# SparkFun_Qwiic_FS3000.net
KiCad netlist of a schematic drawn in EAGLE
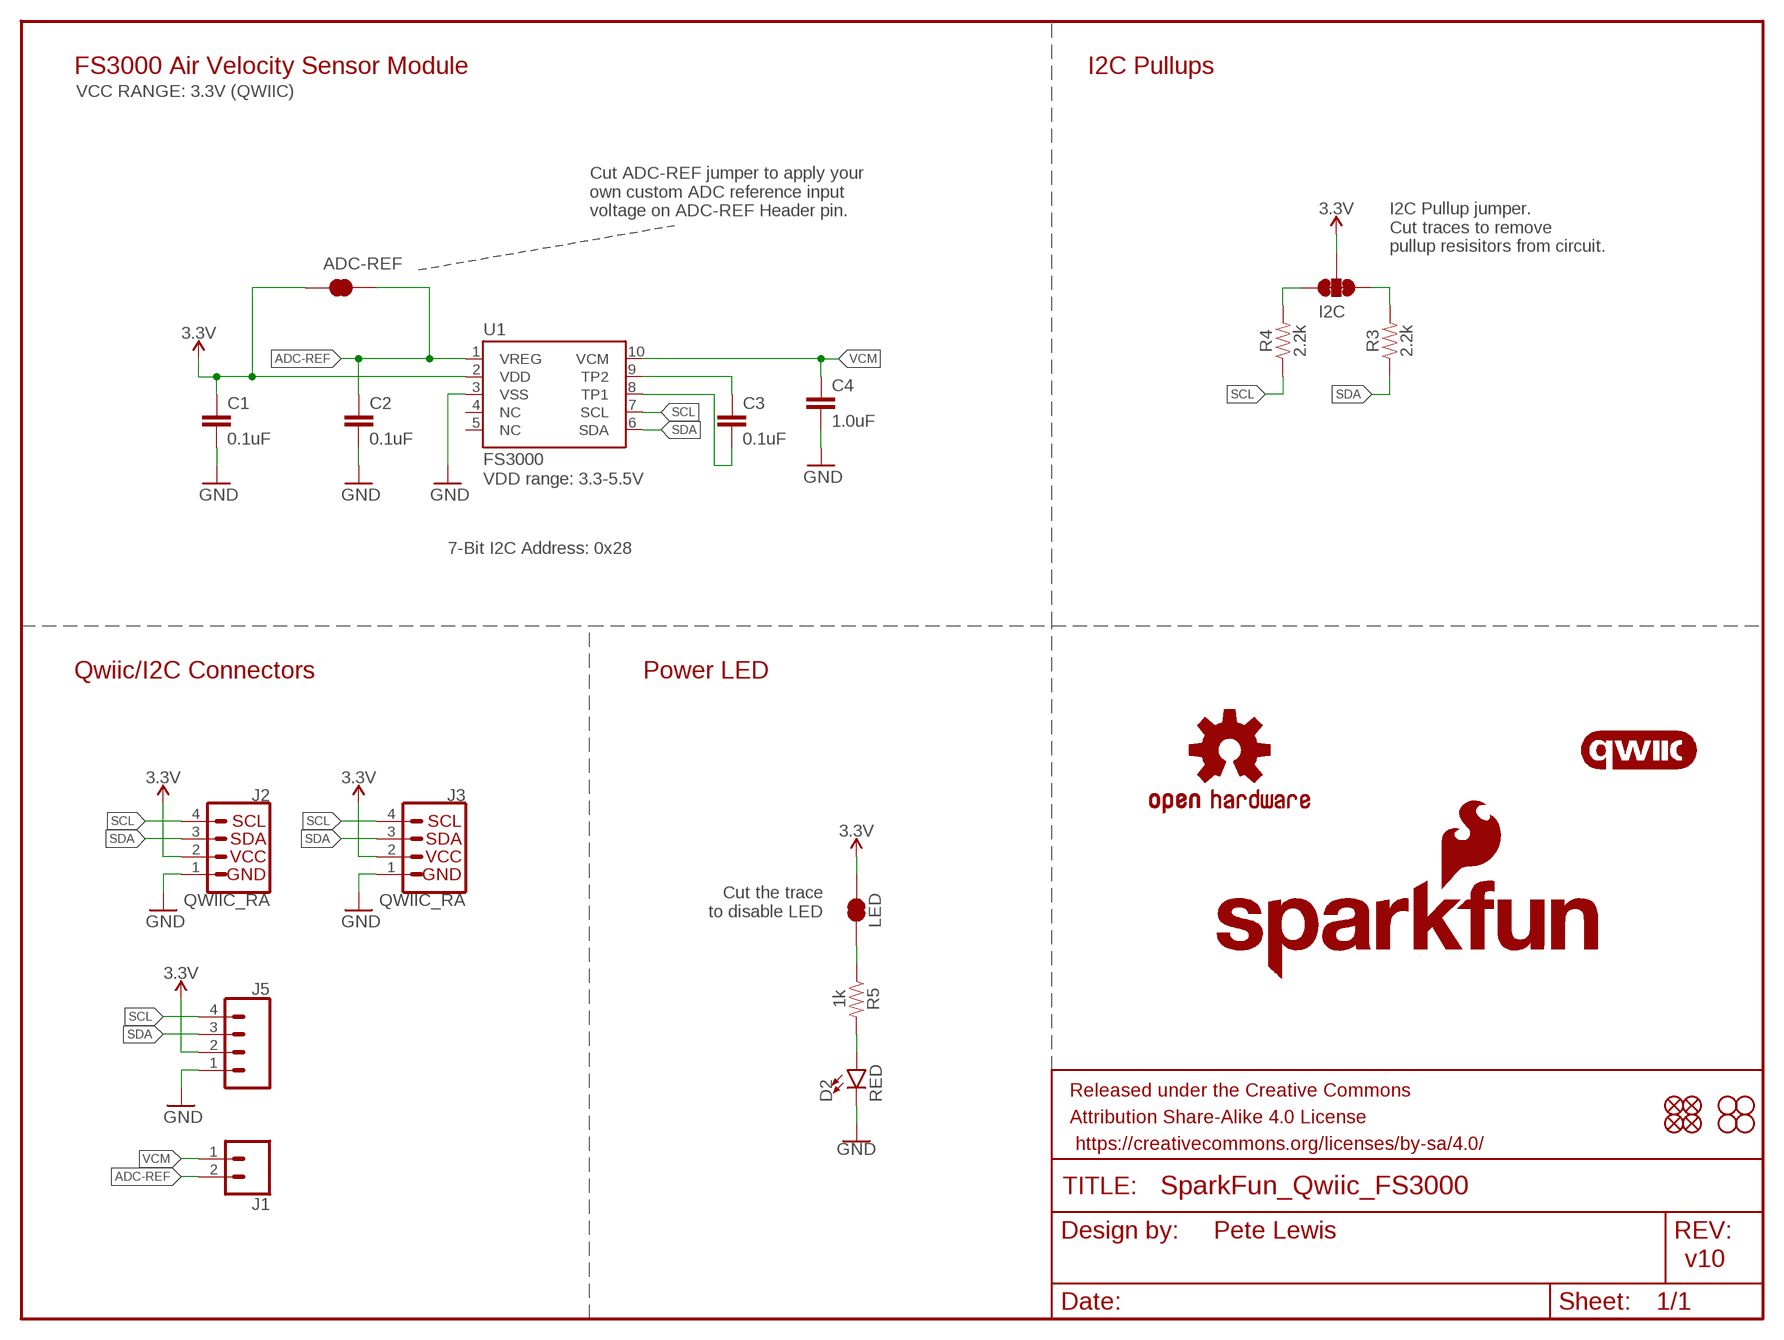
[diagram p0: schematic, sheet 1]

(export (version "E")
  (design (tool "Eeschema 10.0.6"))
  (components
    (comp (ref "ADC-REF")
      (value "JUMPER-SMT_2_NC_TRACE_SILK")
      (footprint "eagle-import:SMT-JUMPER_2_NC_TRACE_SILK")
      (libsource (lib "eagle-import") (part "JUMPER-SMT_2_NC_TRACE_SILK"))
    )
    (comp (ref "C1")
      (value "0.1uF")
      (footprint "eagle-import:0402-TIGHT")
      (libsource (lib "eagle-import") (part "0.1UF-0402T-16V-10%"))
    )
    (comp (ref "C2")
      (value "0.1uF")
      (footprint "eagle-import:0402-TIGHT")
      (libsource (lib "eagle-import") (part "0.1UF-0402T-16V-10%"))
    )
    (comp (ref "C3")
      (value "0.1uF")
      (footprint "eagle-import:0402-TIGHT")
      (libsource (lib "eagle-import") (part "0.1UF-0402T-16V-10%"))
    )
    (comp (ref "C4")
      (value "1.0uF")
      (footprint "eagle-import:0402-TIGHT")
      (libsource (lib "eagle-import") (part "1.0UF-0402T-16V-10%"))
    )
    (comp (ref "D2")
      (value "RED")
      (footprint "eagle-import:LED-0603")
      (libsource (lib "eagle-import") (part "LED-RED0603"))
    )
    (comp (ref "FRAME1")
      (value "FRAME-LETTER")
      (footprint "eagle-import:CREATIVE_COMMONS")
      (libsource (lib "eagle-import") (part "FRAME-LETTER"))
    )
    (comp (ref "I2C")
      (value "JUMPER-SMT_3_2-NC_TRACE_SILK")
      (footprint "eagle-import:SMT-JUMPER_3_2-NC_TRACE_SILK")
      (libsource (lib "eagle-import") (part "JUMPER-SMT_3_2-NC_TRACE_SILK"))
    )
    (comp (ref "J1")
      (value "CONN_021X02_NO_SILK")
      (footprint "eagle-import:1X02_NO_SILK")
      (libsource (lib "eagle-import") (part "CONN_021X02_NO_SILK"))
    )
    (comp (ref "J2")
      (value "QWIIC_RA")
      (footprint "eagle-import:JST04_1MM_RA")
      (libsource (lib "eagle-import") (part "QWIIC_CONNECTORJS-1MM"))
    )
    (comp (ref "J3")
      (value "QWIIC_RA")
      (footprint "eagle-import:JST04_1MM_RA")
      (libsource (lib "eagle-import") (part "QWIIC_CONNECTORJS-1MM"))
    )
    (comp (ref "J5")
      (value "CONN_041X04_NO_SILK")
      (footprint "eagle-import:1X04_NO_SILK")
      (libsource (lib "eagle-import") (part "CONN_041X04_NO_SILK"))
    )
    (comp (ref "JP1")
      (value "LED")
      (footprint "eagle-import:SMT-JUMPER_2_NC_TRACE_SILK")
      (libsource (lib "eagle-import") (part "JUMPER-SMT_2_NC_TRACE_SILK"))
    )
    (comp (ref "JP2")
      (value "FIDUCIALUFIDUCIAL")
      (footprint "eagle-import:FIDUCIAL-MICRO")
      (libsource (lib "eagle-import") (part "FIDUCIALUFIDUCIAL"))
    )
    (comp (ref "JP3")
      (value "STAND-OFF")
      (footprint "eagle-import:STAND-OFF")
      (libsource (lib "eagle-import") (part "STAND-OFF"))
    )
    (comp (ref "JP4")
      (value "STAND-OFF")
      (footprint "eagle-import:STAND-OFF")
      (libsource (lib "eagle-import") (part "STAND-OFF"))
    )
    (comp (ref "JP5")
      (value "FIDUCIALUFIDUCIAL")
      (footprint "eagle-import:FIDUCIAL-MICRO")
      (libsource (lib "eagle-import") (part "FIDUCIALUFIDUCIAL"))
    )
    (comp (ref "JP6")
      (value "FIDUCIALUFIDUCIAL")
      (footprint "eagle-import:FIDUCIAL-MICRO")
      (libsource (lib "eagle-import") (part "FIDUCIALUFIDUCIAL"))
    )
    (comp (ref "JP7")
      (value "STAND-OFF")
      (footprint "eagle-import:STAND-OFF")
      (libsource (lib "eagle-import") (part "STAND-OFF"))
    )
    (comp (ref "JP8")
      (value "STAND-OFF")
      (footprint "eagle-import:STAND-OFF")
      (libsource (lib "eagle-import") (part "STAND-OFF"))
    )
    (comp (ref "JP11")
      (value "FIDUCIALUFIDUCIAL")
      (footprint "eagle-import:FIDUCIAL-MICRO")
      (libsource (lib "eagle-import") (part "FIDUCIALUFIDUCIAL"))
    )
    (comp (ref "LOGO1")
      (value "OSHW-LOGOMINI")
      (footprint "eagle-import:OSHW-LOGO-MINI")
      (libsource (lib "eagle-import") (part "OSHW-LOGOMINI"))
    )
    (comp (ref "LOGO3")
      (value "SFE_LOGO_NAME_FLAME.1_INCH")
      (footprint "eagle-import:SFE_LOGO_NAME_FLAME_.1")
      (libsource (lib "eagle-import") (part "SFE_LOGO_NAME_FLAME.1_INCH"))
    )
    (comp (ref "LOGO4")
      (value "QWIIC_LOGO_5MM")
      (footprint "eagle-import:QWIIC_5MM")
      (libsource (lib "eagle-import") (part "QWIIC_LOGO_5MM"))
    )
    (comp (ref "LOGO5")
      (value "SFE_LOGO_NAME_FLAME.1_INCH")
      (footprint "eagle-import:SFE_LOGO_NAME_FLAME_.1")
      (libsource (lib "eagle-import") (part "SFE_LOGO_NAME_FLAME.1_INCH"))
    )
    (comp (ref "R3")
      (value "2.2k")
      (footprint "eagle-import:0402-TIGHT")
      (libsource (lib "eagle-import") (part "2.2KOHM-0402T-1/16W-1%"))
    )
    (comp (ref "R4")
      (value "2.2k")
      (footprint "eagle-import:0402-TIGHT")
      (libsource (lib "eagle-import") (part "2.2KOHM-0402T-1/16W-1%"))
    )
    (comp (ref "R5")
      (value "1k")
      (footprint "eagle-import:0402-TIGHT")
      (libsource (lib "eagle-import") (part "1KOHM-0402T-1/16W-1%"))
    )
    (comp (ref "U1")
      (value "FS3000")
      (footprint "eagle-import:FS3000")
      (libsource (lib "eagle-import") (part "FS3000"))
    )
  )
  (nets
    (net (code "1") (name "3.3V") (class "Default")
      (node (ref "ADC-REF") (pin "1") (pinfunction "1_1") (pintype "passive"))
      (node (ref "C1") (pin "1") (pinfunction "1_1") (pintype "passive"))
      (node (ref "I2C") (pin "2") (pinfunction "2_2") (pintype "passive"))
      (node (ref "J2") (pin "2") (pinfunction "2_2") (pintype "power_in"))
      (node (ref "J3") (pin "2") (pinfunction "2_2") (pintype "power_in"))
      (node (ref "J5") (pin "2") (pinfunction "2_2") (pintype "passive"))
      (node (ref "JP1") (pin "2") (pinfunction "2_2") (pintype "passive"))
      (node (ref "U1") (pin "2") (pinfunction "VDD_2") (pintype "bidirectional"))
    )
    (net (code "2") (name "ADC-REF") (class "Default")
      (node (ref "ADC-REF") (pin "2") (pinfunction "2_2") (pintype "passive"))
      (node (ref "C2") (pin "1") (pinfunction "1_1") (pintype "passive"))
      (node (ref "J1") (pin "2") (pinfunction "2_2") (pintype "passive"))
      (node (ref "U1") (pin "1") (pinfunction "VREG_1") (pintype "bidirectional"))
    )
    (net (code "3") (name "GND") (class "Default")
      (node (ref "C1") (pin "2") (pinfunction "2_2") (pintype "passive"))
      (node (ref "C2") (pin "2") (pinfunction "2_2") (pintype "passive"))
      (node (ref "C4") (pin "2") (pinfunction "2_2") (pintype "passive"))
      (node (ref "D2") (pin "C") (pinfunction "C_C") (pintype "passive"))
      (node (ref "J2") (pin "1") (pinfunction "1_1") (pintype "power_in"))
      (node (ref "J3") (pin "1") (pinfunction "1_1") (pintype "power_in"))
      (node (ref "J5") (pin "1") (pinfunction "1_1") (pintype "passive"))
      (node (ref "U1") (pin "3") (pinfunction "VSS_3") (pintype "bidirectional"))
    )
    (net (code "4") (name "Net-(D2-PadA)") (class "Default")
      (node (ref "D2") (pin "A") (pinfunction "A_A") (pintype "passive"))
      (node (ref "R5") (pin "2") (pinfunction "2_2") (pintype "passive"))
    )
    (net (code "5") (name "Net-(I2C-Pad1)") (class "Default")
      (node (ref "I2C") (pin "1") (pinfunction "1_1") (pintype "passive"))
      (node (ref "R3") (pin "2") (pinfunction "2_2") (pintype "passive"))
    )
    (net (code "6") (name "Net-(I2C-Pad3)") (class "Default")
      (node (ref "I2C") (pin "3") (pinfunction "3_3") (pintype "passive"))
      (node (ref "R4") (pin "2") (pinfunction "2_2") (pintype "passive"))
    )
    (net (code "7") (name "Net-(JP1-Pad1)") (class "Default")
      (node (ref "JP1") (pin "1") (pinfunction "1_1") (pintype "passive"))
      (node (ref "R5") (pin "1") (pinfunction "1_1") (pintype "passive"))
    )
    (net (code "8") (name "Net-(U1-TP1)") (class "Default")
      (node (ref "C3") (pin "2") (pinfunction "2_2") (pintype "passive"))
      (node (ref "U1") (pin "8") (pinfunction "TP1_8") (pintype "bidirectional"))
    )
    (net (code "9") (name "Net-(U1-TP2)") (class "Default")
      (node (ref "C3") (pin "1") (pinfunction "1_1") (pintype "passive"))
      (node (ref "U1") (pin "9") (pinfunction "TP2_9") (pintype "bidirectional"))
    )
    (net (code "10") (name "SCL") (class "Default")
      (node (ref "J2") (pin "4") (pinfunction "4_4") (pintype "passive"))
      (node (ref "J3") (pin "4") (pinfunction "4_4") (pintype "passive"))
      (node (ref "J5") (pin "4") (pinfunction "4_4") (pintype "passive"))
      (node (ref "R4") (pin "1") (pinfunction "1_1") (pintype "passive"))
      (node (ref "U1") (pin "7") (pinfunction "SCL_7") (pintype "bidirectional"))
    )
    (net (code "11") (name "SDA") (class "Default")
      (node (ref "J2") (pin "3") (pinfunction "3_3") (pintype "passive"))
      (node (ref "J3") (pin "3") (pinfunction "3_3") (pintype "passive"))
      (node (ref "J5") (pin "3") (pinfunction "3_3") (pintype "passive"))
      (node (ref "R3") (pin "1") (pinfunction "1_1") (pintype "passive"))
      (node (ref "U1") (pin "6") (pinfunction "SDA_6") (pintype "bidirectional"))
    )
    (net (code "12") (name "VCM") (class "Default")
      (node (ref "C4") (pin "1") (pinfunction "1_1") (pintype "passive"))
      (node (ref "J1") (pin "1") (pinfunction "1_1") (pintype "passive"))
      (node (ref "U1") (pin "10") (pinfunction "VCM_10") (pintype "bidirectional"))
    )
    (net (code "13") (name "unconnected-(U1-NC-Pad4)") (class "Default")
      (node (ref "U1") (pin "4") (pinfunction "NC_4") (pintype "no_connect"))
    )
    (net (code "14") (name "unconnected-(U1-NC-Pad5)") (class "Default")
      (node (ref "U1") (pin "5") (pinfunction "NC_5") (pintype "no_connect"))
    )
  )
)
